# MainSchematic.net
KiCad netlist of a schematic drawn in Altium Designer
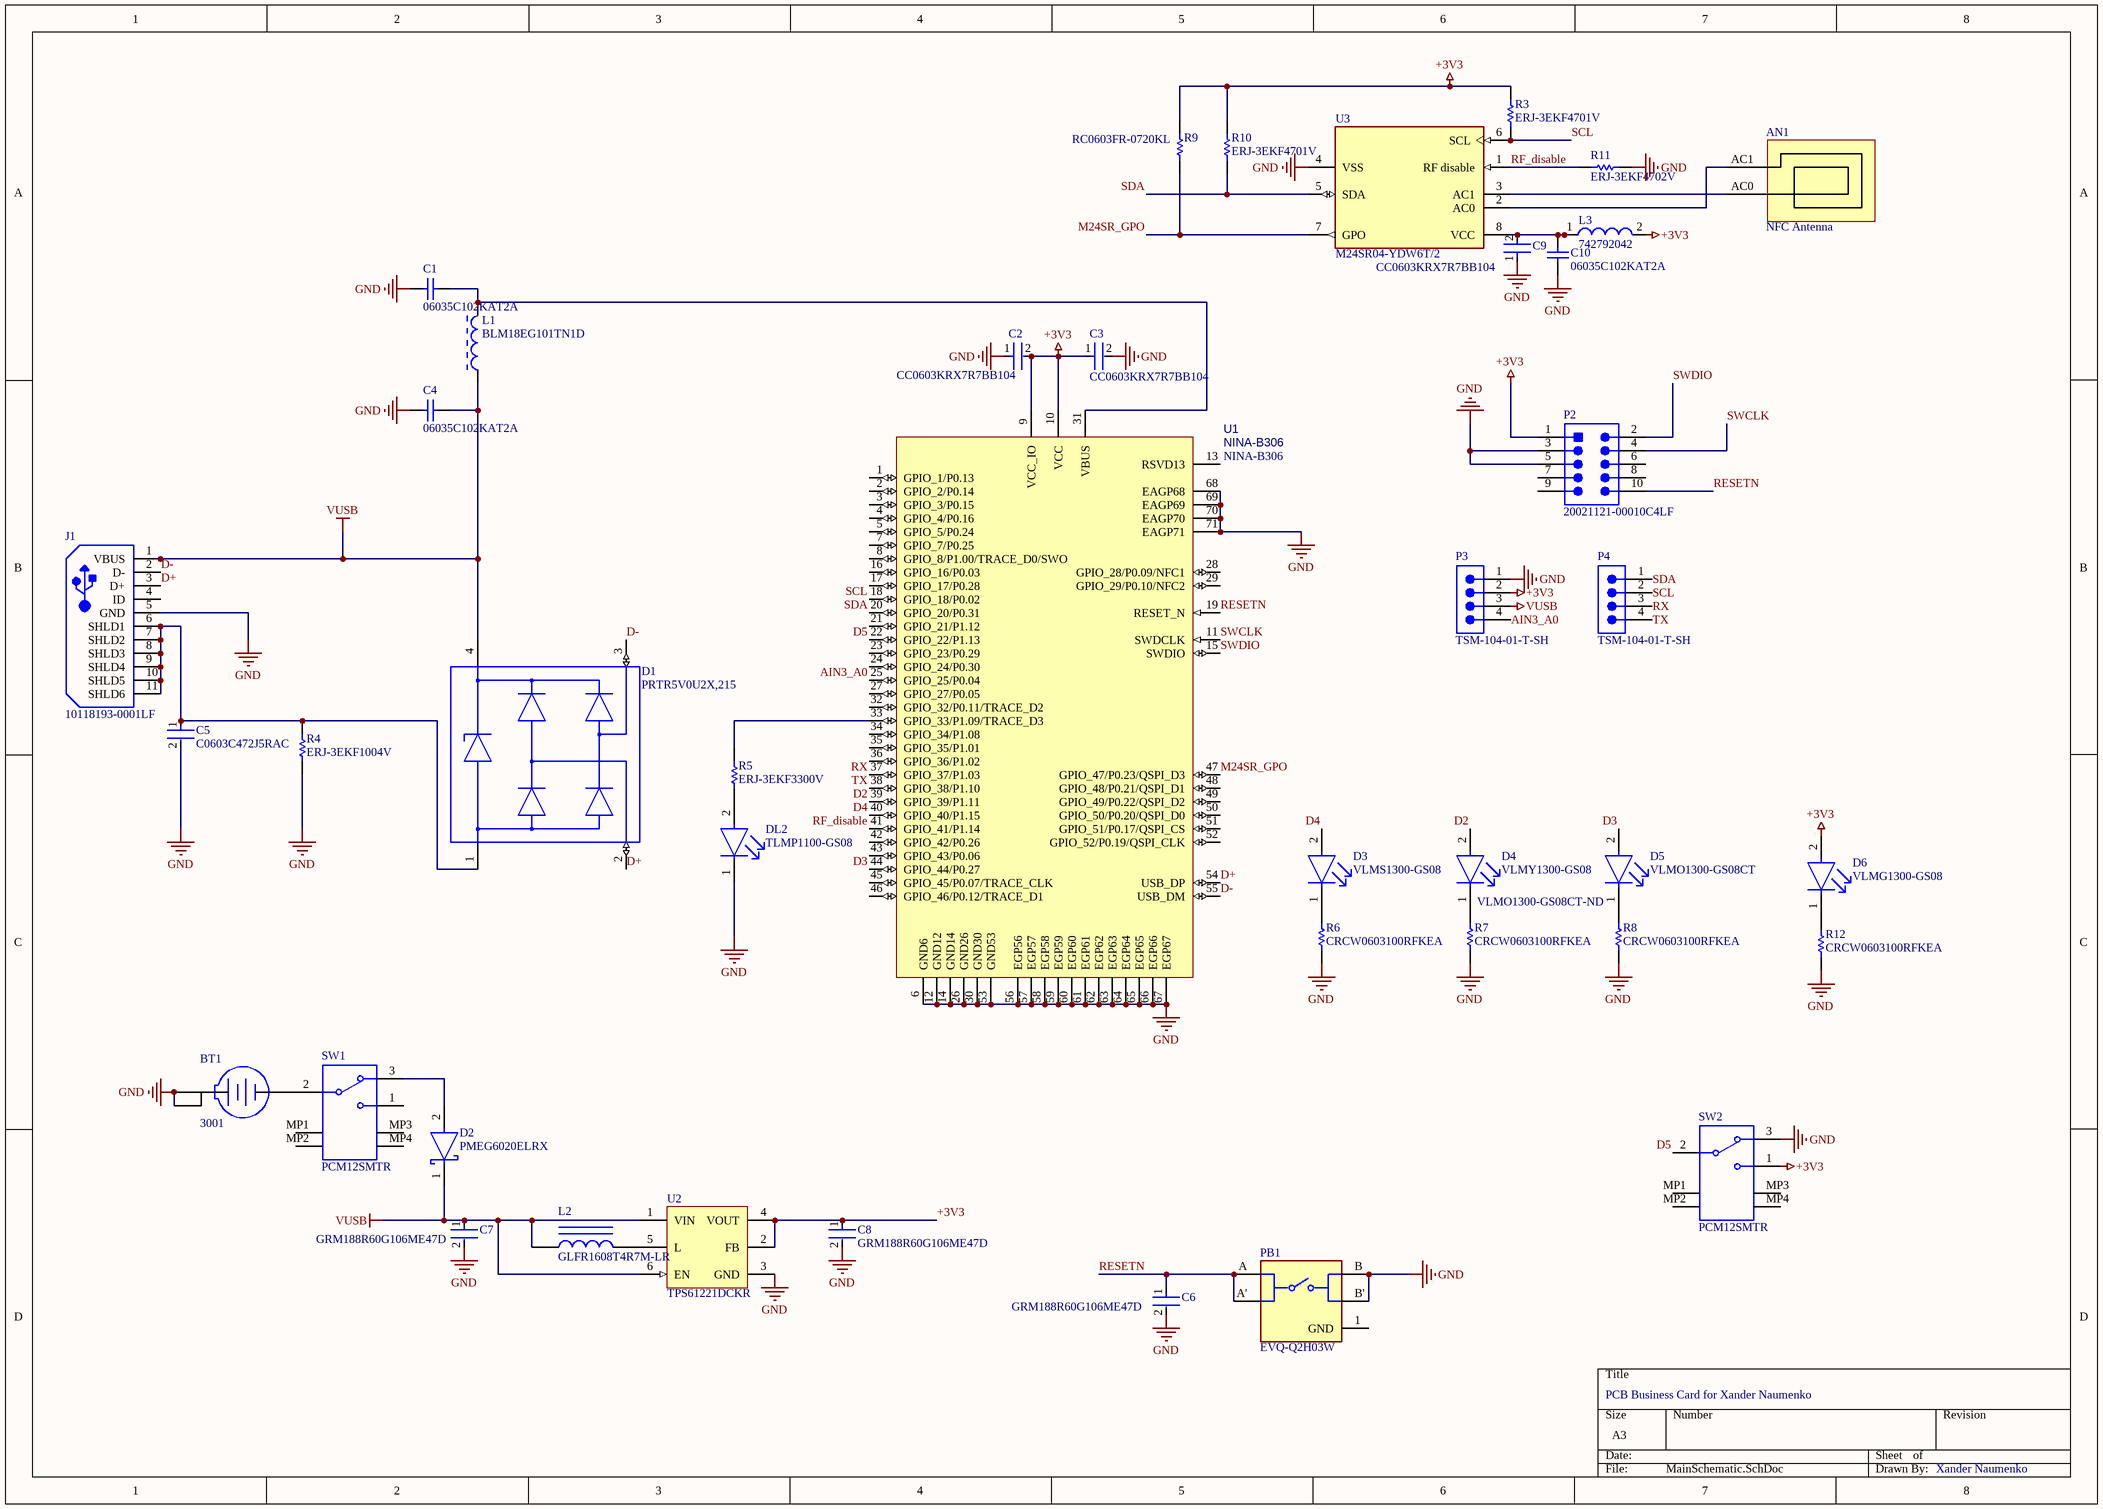
[diagram p0: MainSchematic.SchDoc]

(export (version "E")
  (design (tool "Eeschema 10.0.6"))
  (components
    (comp (ref "AN1")
      (value "NFC Antenna")
      (footprint "NFC_Antenna")
      (description "L=5.51 uH, tuned for 13.56 MHz")
      (libsource (lib "NFC_Antenna") (part "NFC_Antenna"))
    )
    (comp (ref "BT1")
      (value "3001")
      (footprint "KSTN-3001_V")
      (description "Holder Battery Coin, 12 mm, 2-Pin THD, RoHS")
      (fields (field (name "MANUFACTURER") "Keystone"))
      (libsource (lib "Altium Content Vault") (part "BATTERY-HOLDER-COIN-3"))
    )
    (comp (ref "C1")
      (value "06035C102KAT2A")
      (footprint "CAPC1608X90X35LL15T15")
      (fields (field (name "MANUFACTURER") "AVX Interconnect / Elco"))
      (libsource (lib "Altium Content Vault") (part "CAP"))
    )
    (comp (ref "C2")
      (value "CC0603KRX7R7BB104")
      (footprint "FP-CC0603-DA-MFG")
      (description "CAP CER 0.1UF 16V X7R 0603")
      (fields
        (field (name "OCTOPART") "https://octopart.com/cc0603krx7r7bb104-yageo-192941")
        (field (name "TOLERANCE") "0.1")
      )
      (libsource (lib "Altium Content Vault") (part "11868f565c42a9108669ba33697ecf6"))
    )
    (comp (ref "C3")
      (value "CC0603KRX7R7BB104")
      (footprint "FP-CC0603-DA-MFG")
      (description "CAP CER 0.1UF 16V X7R 0603")
      (fields
        (field (name "OCTOPART") "https://octopart.com/cc0603krx7r7bb104-yageo-192941")
        (field (name "TOLERANCE") "0.1")
      )
      (libsource (lib "Altium Content Vault") (part "11868f565c42a9108669ba33697ecf6"))
    )
    (comp (ref "C4")
      (value "06035C102KAT2A")
      (footprint "CAPC1608X90X35LL15T15")
      (fields (field (name "MANUFACTURER") "AVX Interconnect / Elco"))
      (libsource (lib "Altium Content Vault") (part "CAP"))
    )
    (comp (ref "C5")
      (value "C0603C472J5RAC")
      (footprint "FP-C0603C-CF-MFG")
      (description "C0603 4,700 pF X7R 30ppm/°C 5.00% 50 V")
      (fields
        (field (name "OCTOPART") "https://octopart.com/c0603c472j5rac-kemet-965121")
        (field (name "MANUFACTURER") "KEMET")
      )
      (libsource (lib "Altium Content Vault") (part "b4654b650e69147ec39a6b967a45e02"))
    )
    (comp (ref "C6")
      (value "GRM188R60G106ME47D")
      (footprint "FP-GRM188-0_1-e0_2_0_55-IPC_B")
      (description "Chip Multilayer Ceramic Capacitors for General Purpose, 0603, 10uF, X5R, 15%, 20%, 4V")
      (fields (field (name "TOLERANCE") "20%") (field (name "VOLTAGE") "4V"))
      (libsource (lib "Altium Content Vault") (part "02cd4be3c70576c341d710602a673aa"))
    )
    (comp (ref "C7")
      (value "GRM188R60G106ME47D")
      (footprint "FP-GRM188-0_1-e0_2_0_55-IPC_B")
      (description "Chip Multilayer Ceramic Capacitors for General Purpose, 0603, 10uF, X5R, 15%, 20%, 4V")
      (fields (field (name "TOLERANCE") "20%") (field (name "VOLTAGE") "4V"))
      (libsource (lib "Altium Content Vault") (part "02cd4be3c70576c341d710602a673aa"))
    )
    (comp (ref "C8")
      (value "GRM188R60G106ME47D")
      (footprint "FP-GRM188-0_1-e0_2_0_55-IPC_B")
      (description "Chip Multilayer Ceramic Capacitors for General Purpose, 0603, 10uF, X5R, 15%, 20%, 4V")
      (fields (field (name "TOLERANCE") "20%") (field (name "VOLTAGE") "4V"))
      (libsource (lib "Altium Content Vault") (part "02cd4be3c70576c341d710602a673aa"))
    )
    (comp (ref "C9")
      (value "CC0603KRX7R7BB104")
      (footprint "FP-CC0603-DA-MFG")
      (description "CAP CER 0.1UF 16V X7R 0603")
      (fields
        (field (name "OCTOPART") "https://octopart.com/cc0603krx7r7bb104-yageo-192941")
        (field (name "TOLERANCE") "0.1")
      )
      (libsource (lib "Altium Content Vault") (part "11868f565c42a9108669ba33697ecf6"))
    )
    (comp (ref "C10")
      (value "06035C102KAT2A")
      (footprint "CAPC1608X90X35LL15T15")
      (fields (field (name "MANUFACTURER") "AVX Interconnect / Elco"))
      (libsource (lib "Altium Content Vault") (part "CAP"))
    )
    (comp (ref "D1")
      (value "PRTR5V0U2X,215")
      (footprint "FP-SOT143B-MFG")
      (description "TVS DIODE 5.5V SOT143B")
      (fields (field (name "MANUFACTURER") "Nexperia"))
      (libsource (lib "Altium Content Vault") (part "31e4fa1655694efd507c8a671e666ef"))
    )
    (comp (ref "D2")
      (value "PMEG6020ELRX")
      (footprint "FP-SOD123W-MFG")
      (description "DIODE SCHOTTKY 60V 2A SOD123W")
      (libsource (lib "Altium Content Vault") (part "1d6ec82d83fb6aee721767c19dac4b9"))
    )
    (comp (ref "D3")
      (value "VLMS1300-GS08")
      (footprint "FP-6_541-5092_01-4-MFG")
      (description "Red 631nm LED Indication - Discrete 2V 0603 (1608 Metric)")
      (fields (field (name "MANUFACTURER") "Vishay"))
      (libsource (lib "Altium Content Vault") (part "8706943c75ba83719d021d2fdc84c58"))
    )
    (comp (ref "D4")
      (value "VLMY1300-GS08")
      (footprint "FP-6_541-5092_01-4-MFG")
      (description "LED YELLOW 0603 SMD")
      (fields
        (field (name "OCTOPART") "https://octopart.com/vlmy1300-gs08-vishay-21709204")
        (field (name "MANUFACTURER") "Vishay")
        (field (name "SUPPLIER PART NUMBER 1") "VLMO1300-GS08CT-ND")
      )
      (libsource (lib "Altium Content Vault") (part "8706943c75ba83719d021d2fdc84c58"))
    )
    (comp (ref "D5")
      (value "VLMO1300-GS08CT")
      (footprint "FP-6_541-5092_01-4-MFG")
      (description "LED YELLOW 0603 SMD")
      (fields
        (field (name "OCTOPART") "https://octopart.com/vlmy1300-gs08-vishay-21709204")
        (field (name "MANUFACTURER") "Vishay")
      )
      (libsource (lib "Altium Content Vault") (part "8706943c75ba83719d021d2fdc84c58"))
    )
    (comp (ref "D6")
      (value "VLMG1300-GS08")
      (footprint "FP-6_541-5092_01-4-MFG")
      (description "Green 571nm LED Indication - Discrete 2V 0603 (1608 Metric)")
      (fields (field (name "OCTOPART") "https://octopart.com/vlmg1300-gs08-vishay-21709199"))
      (libsource (lib "Altium Content Vault") (part "8706943c75ba83719d021d2fdc84c58"))
    )
    (comp (ref "DL2")
      (value "TLMP1100-GS08")
      (footprint "FP-6_541-5056_01-4-MFG")
      (description "LED GREEN 0603 SMD")
      (fields
        (field (name "MANUFACTURER") "Vishay")
        (field (name "OCTOPART") "https://octopart.com/tlmp1100-gs08-vishay-55433993")
      )
      (libsource (lib "Altium Content Vault") (part "8706943c75ba83719d021d2fdc84c58"))
    )
    (comp (ref "J1")
      (value "10118193-0001LF")
      (footprint "FCI-10118193-0001LF-5_V")
      (description "Micro USB B Type Receptacle, -55 to 85 degC, 5-Pin SMD, RoHS, Tape and Reel")
      (fields (field (name "MANUFACTURER") "FCI"))
      (libsource (lib "Altium Content Vault") (part "USB-5-6SHLD"))
    )
    (comp (ref "L1")
      (value "BLM18EG101TN1D")
      (footprint "MURA-BLM18-RF-H3-CHIP-2_V")
      (fields (field (name "MANUFACTURER") "Murata"))
      (libsource (lib "Altium Content Vault") (part "MURA-FB-2"))
    )
    (comp (ref "L2")
      (value "GLFR1608T4R7M-LR")
      (footprint "INDC1608X100X35LL20T15")
      (description "Chip Inductor, 4.7 uH, +/- 20%, -40 to 105 degC, 0603 (1608 Metric), RoHS, Tape and Reel")
      (fields (field (name "MANUFACTURER") "TDK") (field (name "TOLERANCE") "±20%"))
      (libsource (lib "Altium Content Vault") (part "IND-DOT-2_A"))
    )
    (comp (ref "L3")
      (value "742792042")
      (footprint "SMD-0805")
      (description "SMD EMI Suppression Ferrite Bead WE-CBF, Z = 600 Ohm")
      (libsource (lib "Altium Content Vault") (part "PAS-IND-INDUCTOR-2"))
    )
    (comp (ref "P2")
      (value "20021121-00010C4LF")
      (footprint "HDR2X5_SMT")
      (description "Male Header, Pitch 1.27 mm, 2 x 5 Position, Height 4.55 mm, -40 to 85 degC, RoHS, Tape and Reel")
      (fields (field (name "MANUFACTURER") "FCI"))
      (libsource (lib "Altium Content Vault") (part "CN-2P-M-R10"))
    )
    (comp (ref "P3")
      (value "TSM-104-01-T-SH")
      (footprint "SMTC-TSM-104-01-X-SH")
      (fields (field (name "MANUFACTURER") "Samtec"))
      (libsource (lib "Altium Content Vault") (part "SMTC-TSM-104-01-X-SH"))
    )
    (comp (ref "P4")
      (value "TSM-104-01-T-SH")
      (footprint "SMTC-TSM-104-01-X-SH")
      (fields (field (name "MANUFACTURER") "Samtec"))
      (libsource (lib "Altium Content Vault") (part "SMTC-TSM-104-01-X-SH"))
    )
    (comp (ref "PB1")
      (value "EVQ-Q2H03W")
      (footprint "FP-EVQ-Q2H03W-MFG")
      (description "SWITCH TACTILE SPST-NO 0.02A 15V")
      (fields
        (field (name "OCTOPART") "https://octopart.com/evq-q2h03w-panasonic-1368538")
        (field (name "MANUFACTURER") "Panasonic Electronic Components")
      )
      (libsource (lib "Altium Content Vault") (part "771f9546cad75bebae6a9b98152ef8d"))
    )
    (comp (ref "R3")
      (value "ERJ-3EKF4701V")
      (footprint "RESC1608X55X30NL15T15")
      (fields (field (name "TOLERANCE") "5%"))
      (libsource (lib "Altium Content Vault") (part "RES-2"))
    )
    (comp (ref "R4")
      (value "ERJ-3EKF1004V")
      (footprint "RESC1608X55X30LL15T15")
      (fields (field (name "MANUFACTURER") "Panasonic"))
      (libsource (lib "Altium Content Vault") (part "RES"))
    )
    (comp (ref "R5")
      (value "ERJ-3EKF3300V")
      (footprint "RESC1608X55X30LL15T15")
      (description "Chip Resistor, 330 Ohm, +/- 1%, 0.1 W, -55 to 155 degC, 0603 (1608 Metric), RoHS, Tape and Reel")
      (libsource (lib "Altium Content Vault") (part "RES-2"))
    )
    (comp (ref "R6")
      (value "CRCW0603100RFKEA")
      (footprint "RESC1609X50X30ML8T20")
      (description "Chip Resistor, 100 Ohm, +/- 1%, 100 mW,-55 to 155 degC, 0603 (1608 Metric), RoHS, Tape and Ree")
      (fields (field (name "MANUFACTURER") "Vishay Semiconductor"))
      (libsource (lib "Altium Content Vault") (part "RES-2"))
    )
    (comp (ref "R7")
      (value "CRCW0603100RFKEA")
      (footprint "RESC1609X50X30ML8T20")
      (description "Chip Resistor, 100 Ohm, +/- 1%, 100 mW,-55 to 155 degC, 0603 (1608 Metric), RoHS, Tape and Ree")
      (fields (field (name "MANUFACTURER") "Vishay Semiconductor"))
      (libsource (lib "Altium Content Vault") (part "RES-2"))
    )
    (comp (ref "R8")
      (value "CRCW0603100RFKEA")
      (footprint "RESC1609X50X30ML8T20")
      (description "Chip Resistor, 100 Ohm, +/- 1%, 100 mW,-55 to 155 degC, 0603 (1608 Metric), RoHS, Tape and Ree")
      (fields (field (name "MANUFACTURER") "Vishay Semiconductor"))
      (libsource (lib "Altium Content Vault") (part "RES-2"))
    )
    (comp (ref "R9")
      (value "RC0603FR-0720KL")
      (footprint "RESC1608X55X25LL10T15")
      (description "Chip Resistor, 20 KOhm, +/- 1%, 0.1 W, -55 to 155 degC, 0603 (1608 Metric), RoHS, Tape and Reel")
      (fields (field (name "MANUFACTURER") "Yageo") (field (name "TOLERANCE") "1%"))
      (libsource (lib "Altium Content Vault") (part "RES-2"))
    )
    (comp (ref "R10")
      (value "ERJ-3EKF4701V")
      (footprint "RESC1608X55X30NL15T15")
      (fields (field (name "TOLERANCE") "5%"))
      (libsource (lib "Altium Content Vault") (part "RES-2"))
    )
    (comp (ref "R11")
      (value "ERJ-3EKF4702V")
      (footprint "RESC1608X55X30NL15T15")
      (description "Chip Resistor, 47 KOhm, +/- 1%, 0.1 W, -55 to 155 degC, 0603 (1608 Metric), RoHS, Tape and Reel")
      (libsource (lib "Altium Content Vault") (part "RES-2"))
    )
    (comp (ref "R12")
      (value "CRCW0603100RFKEA")
      (footprint "RESC1609X50X30ML8T20")
      (description "Chip Resistor, 100 Ohm, +/- 1%, 100 mW,-55 to 155 degC, 0603 (1608 Metric), RoHS, Tape and Ree")
      (fields (field (name "MANUFACTURER") "Vishay Semiconductor"))
      (libsource (lib "Altium Content Vault") (part "RES-2"))
    )
    (comp (ref "SW1")
      (value "PCM12SMTR")
      (footprint "CKCP-PCM12SMTR_V")
      (description "Ultraminiature Slide Switch, SPDT, 0.3 A, 6 V, -20 to 85 degC, 3-Pin SMD, RoHS, Tape and Reel")
      (fields (field (name "MANUFACTURER") "C&K Components"))
      (libsource (lib "Altium Content Vault") (part "SW-SPDT-3_A"))
    )
    (comp (ref "SW2")
      (value "PCM12SMTR")
      (footprint "CKCP-PCM12SMTR_V")
      (description "Ultraminiature Slide Switch, SPDT, 0.3 A, 6 V, -20 to 85 degC, 3-Pin SMD, RoHS, Tape and Reel")
      (fields (field (name "MANUFACTURER") "C&K Components"))
      (libsource (lib "Altium Content Vault") (part "SW-SPDT-3_A"))
    )
    (comp (ref "U1")
      (value "NINA-B306")
      (footprint "NINA_LGA71R_1500X1000X223_PCB")
      (description "Stand-alone Bluetooth low energy module")
      (fields (field (name "MANUFACTURER") "u-blox") (field (name "ALTIUM_VALUE") "NINA-B306"))
      (libsource (lib "ubloxLib") (part "NINA-B306"))
    )
    (comp (ref "U2")
      (value "TPS61221DCKR")
      (footprint "DCK0006A_L")
      (fields (field (name "MANUFACTURER") "Texas Instruments"))
      (libsource (lib "Altium Content Vault") (part "TI-TPS61221DCK6"))
    )
    (comp (ref "U3")
      (value "M24SR04-YDW6T/2")
      (footprint "FP-TSSOP8-AM-IPC_C")
      (description "IC RFID TRANSP 13.56MHZ 8TSSOP")
      (fields
        (field (name "OCTOPART") "https://octopart.com/m24sr04-ydw6t%2F2-stmicroelectronics-31443742")
        (field (name "MANUFACTURER") "STMicroelectronics")
      )
      (libsource (lib "Altium Content Vault") (part "34dd642e2aae41d6824d9e49441a900"))
    )
  )
  (nets
    (net (code "1") (name "+3V3") (class "Default")
      (node (ref "C2") (pin "2") (pinfunction "2_2") (pintype "passive"))
      (node (ref "C3") (pin "1") (pinfunction "1_1") (pintype "passive"))
      (node (ref "C8") (pin "1") (pinfunction "1_1") (pintype "passive"))
      (node (ref "D6") (pin "2") (pinfunction "A_2") (pintype "passive"))
      (node (ref "L3") (pin "2") (pinfunction "2_2") (pintype "passive"))
      (node (ref "P2") (pin "1") (pinfunction "1_1") (pintype "passive"))
      (node (ref "P3") (pin "2") (pinfunction "2_2") (pintype "passive"))
      (node (ref "R10") (pin "2") (pinfunction "2_2") (pintype "passive"))
      (node (ref "R3") (pin "2") (pinfunction "2_2") (pintype "passive"))
      (node (ref "R9") (pin "2") (pinfunction "2_2") (pintype "passive"))
      (node (ref "SW2") (pin "1") (pinfunction "1_1") (pintype "passive"))
      (node (ref "U1") (pin "10") (pinfunction "VCC_10") (pintype "power_in"))
      (node (ref "U1") (pin "9") (pinfunction "VCC_IO_9") (pintype "power_in"))
      (node (ref "U2") (pin "2") (pinfunction "FB_2") (pintype "passive"))
      (node (ref "U2") (pin "4") (pinfunction "VOUT_4") (pintype "power_in"))
    )
    (net (code "2") (name "/AIN3_A0") (class "Default")
      (node (ref "P3") (pin "4") (pinfunction "4_4") (pintype "passive"))
      (node (ref "U1") (pin "25") (pinfunction "GPIO_25/P0.04_25") (pintype "bidirectional"))
    )
    (net (code "3") (name "/D+") (class "Default")
      (node (ref "D1") (pin "2") (pinfunction "I/O_1_2") (pintype "bidirectional"))
      (node (ref "J1") (pin "3") (pinfunction "D+_3") (pintype "passive"))
      (node (ref "U1") (pin "54") (pinfunction "USB_DP_54") (pintype "bidirectional"))
    )
    (net (code "4") (name "/D-") (class "Default")
      (node (ref "D1") (pin "3") (pinfunction "I/O_2_3") (pintype "bidirectional"))
      (node (ref "J1") (pin "2") (pinfunction "D-_2") (pintype "passive"))
      (node (ref "U1") (pin "55") (pinfunction "USB_DM_55") (pintype "bidirectional"))
    )
    (net (code "5") (name "/D2") (class "Default")
      (node (ref "D4") (pin "2") (pinfunction "A_2") (pintype "passive"))
      (node (ref "U1") (pin "39") (pinfunction "GPIO_39/P1.11_39") (pintype "bidirectional"))
    )
    (net (code "6") (name "/D3") (class "Default")
      (node (ref "D5") (pin "2") (pinfunction "A_2") (pintype "passive"))
      (node (ref "U1") (pin "44") (pinfunction "GPIO_44/P0.27_44") (pintype "bidirectional"))
    )
    (net (code "7") (name "/D4") (class "Default")
      (node (ref "D3") (pin "2") (pinfunction "A_2") (pintype "passive"))
      (node (ref "U1") (pin "40") (pinfunction "GPIO_40/P1.15_40") (pintype "bidirectional"))
    )
    (net (code "8") (name "/D5") (class "Default")
      (node (ref "SW2") (pin "2") (pinfunction "2_2") (pintype "passive"))
      (node (ref "U1") (pin "22") (pinfunction "GPIO_22/P1.13_22") (pintype "bidirectional"))
    )
    (net (code "9") (name "/M24SR_GPO") (class "Default")
      (node (ref "R9") (pin "1") (pinfunction "1_1") (pintype "passive"))
      (node (ref "U1") (pin "47") (pinfunction "GPIO_47/P0.23/QSPI_D3_47") (pintype "bidirectional"))
      (node (ref "U3") (pin "7") (pinfunction "GPO_7") (pintype "output"))
    )
    (net (code "10") (name "/RESETN") (class "Default")
      (node (ref "C6") (pin "1") (pinfunction "1_1") (pintype "passive"))
      (node (ref "P2") (pin "10") (pinfunction "10_10") (pintype "passive"))
      (node (ref "PB1") (pin "A") (pinfunction "A_A") (pintype "passive"))
      (node (ref "PB1") (pin "A'") (pinfunction "A'_A'") (pintype "passive"))
      (node (ref "U1") (pin "19") (pinfunction "RESET_N_19") (pintype "input"))
    )
    (net (code "11") (name "/RF_disable") (class "Default")
      (node (ref "R11") (pin "1") (pinfunction "1_1") (pintype "passive"))
      (node (ref "U1") (pin "41") (pinfunction "GPIO_41/P1.14_41") (pintype "bidirectional"))
      (node (ref "U3") (pin "1") (pinfunction "RF_disable_1") (pintype "input"))
    )
    (net (code "12") (name "/RX") (class "Default")
      (node (ref "P4") (pin "3") (pinfunction "3_3") (pintype "passive"))
      (node (ref "U1") (pin "37") (pinfunction "GPIO_37/P1.03_37") (pintype "bidirectional"))
    )
    (net (code "13") (name "/SCL") (class "Default")
      (node (ref "P4") (pin "2") (pinfunction "2_2") (pintype "passive"))
      (node (ref "R3") (pin "1") (pinfunction "1_1") (pintype "passive"))
      (node (ref "U1") (pin "18") (pinfunction "GPIO_18/P0.02_18") (pintype "bidirectional"))
      (node (ref "U3") (pin "6") (pinfunction "SCL_6") (pintype "input"))
    )
    (net (code "14") (name "/SDA") (class "Default")
      (node (ref "P4") (pin "1") (pinfunction "1_1") (pintype "passive"))
      (node (ref "R10") (pin "1") (pinfunction "1_1") (pintype "passive"))
      (node (ref "U1") (pin "20") (pinfunction "GPIO_20/P0.31_20") (pintype "bidirectional"))
      (node (ref "U3") (pin "5") (pinfunction "SDA_5") (pintype "bidirectional"))
    )
    (net (code "15") (name "/SWCLK") (class "Default")
      (node (ref "P2") (pin "4") (pinfunction "4_4") (pintype "passive"))
      (node (ref "U1") (pin "11") (pinfunction "SWDCLK_11") (pintype "input"))
    )
    (net (code "16") (name "/SWDIO") (class "Default")
      (node (ref "P2") (pin "2") (pinfunction "2_2") (pintype "passive"))
      (node (ref "U1") (pin "15") (pinfunction "SWDIO_15") (pintype "bidirectional"))
    )
    (net (code "17") (name "/TX") (class "Default")
      (node (ref "P4") (pin "4") (pinfunction "4_4") (pintype "passive"))
      (node (ref "U1") (pin "38") (pinfunction "GPIO_38/P1.10_38") (pintype "bidirectional"))
    )
    (net (code "18") (name "GND") (class "Default")
      (node (ref "BT1") (pin "1") (pinfunction "+_1") (pintype "passive"))
      (node (ref "BT1") (pin "2") (pinfunction "+_2") (pintype "passive"))
      (node (ref "C1") (pin "1") (pinfunction "1_1") (pintype "passive"))
      (node (ref "C10") (pin "1") (pinfunction "1_1") (pintype "passive"))
      (node (ref "C2") (pin "1") (pinfunction "1_1") (pintype "passive"))
      (node (ref "C3") (pin "2") (pinfunction "2_2") (pintype "passive"))
      (node (ref "C4") (pin "1") (pinfunction "1_1") (pintype "passive"))
      (node (ref "C5") (pin "2") (pinfunction "2_2") (pintype "passive"))
      (node (ref "C6") (pin "2") (pinfunction "2_2") (pintype "passive"))
      (node (ref "C7") (pin "2") (pinfunction "2_2") (pintype "passive"))
      (node (ref "C8") (pin "2") (pinfunction "2_2") (pintype "passive"))
      (node (ref "C9") (pin "1") (pinfunction "1_1") (pintype "passive"))
      (node (ref "DL2") (pin "1") (pinfunction "C_1") (pintype "passive"))
      (node (ref "J1") (pin "5") (pinfunction "GND_5") (pintype "passive"))
      (node (ref "P2") (pin "3") (pinfunction "3_3") (pintype "passive"))
      (node (ref "P2") (pin "5") (pinfunction "5_5") (pintype "passive"))
      (node (ref "P3") (pin "1") (pinfunction "1_1") (pintype "passive"))
      (node (ref "PB1") (pin "B") (pinfunction "B_B") (pintype "passive"))
      (node (ref "PB1") (pin "B'") (pinfunction "B'_B'") (pintype "passive"))
      (node (ref "R11") (pin "2") (pinfunction "2_2") (pintype "passive"))
      (node (ref "R12") (pin "1") (pinfunction "1_1") (pintype "passive"))
      (node (ref "R4") (pin "1") (pinfunction "1_1") (pintype "passive"))
      (node (ref "R6") (pin "1") (pinfunction "1_1") (pintype "passive"))
      (node (ref "R7") (pin "1") (pinfunction "1_1") (pintype "passive"))
      (node (ref "R8") (pin "1") (pinfunction "1_1") (pintype "passive"))
      (node (ref "SW2") (pin "3") (pinfunction "3_3") (pintype "passive"))
      (node (ref "U1") (pin "12") (pinfunction "GND12_12") (pintype "power_in"))
      (node (ref "U1") (pin "14") (pinfunction "GND14_14") (pintype "power_in"))
      (node (ref "U1") (pin "26") (pinfunction "GND26_26") (pintype "power_in"))
      (node (ref "U1") (pin "30") (pinfunction "GND30_30") (pintype "power_in"))
      (node (ref "U1") (pin "53") (pinfunction "GND53_53") (pintype "power_in"))
      (node (ref "U1") (pin "56") (pinfunction "EGP56_56") (pintype "power_in"))
      (node (ref "U1") (pin "57") (pinfunction "EGP57_57") (pintype "power_in"))
      (node (ref "U1") (pin "58") (pinfunction "EGP58_58") (pintype "power_in"))
      (node (ref "U1") (pin "59") (pinfunction "EGP59_59") (pintype "power_in"))
      (node (ref "U1") (pin "6") (pinfunction "GND6_6") (pintype "power_in"))
      (node (ref "U1") (pin "60") (pinfunction "EGP60_60") (pintype "power_in"))
      (node (ref "U1") (pin "61") (pinfunction "EGP61_61") (pintype "power_in"))
      (node (ref "U1") (pin "62") (pinfunction "EGP62_62") (pintype "power_in"))
      (node (ref "U1") (pin "63") (pinfunction "EGP63_63") (pintype "power_in"))
      (node (ref "U1") (pin "64") (pinfunction "EGP64_64") (pintype "power_in"))
      (node (ref "U1") (pin "65") (pinfunction "EGP65_65") (pintype "power_in"))
      (node (ref "U1") (pin "66") (pinfunction "EGP66_66") (pintype "power_in"))
      (node (ref "U1") (pin "67") (pinfunction "EGP67_67") (pintype "power_in"))
      (node (ref "U1") (pin "68") (pinfunction "EAGP68_68") (pintype "power_in"))
      (node (ref "U1") (pin "69") (pinfunction "EAGP69_69") (pintype "power_in"))
      (node (ref "U1") (pin "70") (pinfunction "EAGP70_70") (pintype "power_in"))
      (node (ref "U1") (pin "71") (pinfunction "EAGP71_71") (pintype "power_in"))
      (node (ref "U2") (pin "3") (pinfunction "GND_3") (pintype "power_in"))
      (node (ref "U3") (pin "4") (pinfunction "VSS_4") (pintype "power_in"))
    )
    (net (code "19") (name "Net-(BT1--)") (class "Default")
      (node (ref "BT1") (pin "3") (pinfunction "-_3") (pintype "passive"))
      (node (ref "SW1") (pin "2") (pinfunction "2_2") (pintype "passive"))
    )
    (net (code "20") (name "Net-(D1-GND)") (class "Default")
      (node (ref "C5") (pin "1") (pinfunction "1_1") (pintype "passive"))
      (node (ref "D1") (pin "1") (pinfunction "GND_1") (pintype "power_in"))
      (node (ref "J1") (pin "10") (pinfunction "SHLD5_10") (pintype "passive"))
      (node (ref "J1") (pin "11") (pinfunction "SHLD6_11") (pintype "passive"))
      (node (ref "J1") (pin "6") (pinfunction "SHLD1_6") (pintype "passive"))
      (node (ref "J1") (pin "7") (pinfunction "SHLD2_7") (pintype "passive"))
      (node (ref "J1") (pin "8") (pinfunction "SHLD3_8") (pintype "passive"))
      (node (ref "J1") (pin "9") (pinfunction "SHLD4_9") (pintype "passive"))
      (node (ref "R4") (pin "2") (pinfunction "2_2") (pintype "passive"))
    )
    (net (code "21") (name "Net-(D2-A)") (class "Default")
      (node (ref "D2") (pin "2") (pinfunction "A_2") (pintype "passive"))
      (node (ref "SW1") (pin "3") (pinfunction "3_3") (pintype "passive"))
    )
    (net (code "22") (name "Net-(D3-C)") (class "Default")
      (node (ref "D3") (pin "1") (pinfunction "C_1") (pintype "passive"))
      (node (ref "R6") (pin "2") (pinfunction "2_2") (pintype "passive"))
    )
    (net (code "23") (name "Net-(D4-C)") (class "Default")
      (node (ref "D4") (pin "1") (pinfunction "C_1") (pintype "passive"))
      (node (ref "R7") (pin "2") (pinfunction "2_2") (pintype "passive"))
    )
    (net (code "24") (name "Net-(D5-C)") (class "Default")
      (node (ref "D5") (pin "1") (pinfunction "C_1") (pintype "passive"))
      (node (ref "R8") (pin "2") (pinfunction "2_2") (pintype "passive"))
    )
    (net (code "25") (name "Net-(D6-C)") (class "Default")
      (node (ref "D6") (pin "1") (pinfunction "C_1") (pintype "passive"))
      (node (ref "R12") (pin "2") (pinfunction "2_2") (pintype "passive"))
    )
    (net (code "26") (name "Net-(DL2-A)") (class "Default")
      (node (ref "DL2") (pin "2") (pinfunction "A_2") (pintype "passive"))
      (node (ref "R5") (pin "1") (pinfunction "1_1") (pintype "passive"))
    )
    (net (code "27") (name "Net-(U1-GPIO_33{slash}P1.09{slash}TRACE_D3)") (class "Default")
      (node (ref "R5") (pin "2") (pinfunction "2_2") (pintype "passive"))
      (node (ref "U1") (pin "33") (pinfunction "GPIO_33/P1.09/TRACE_D3_33") (pintype "bidirectional"))
    )
    (net (code "28") (name "Net-(U1-VBUS)") (class "Default")
      (node (ref "C1") (pin "2") (pinfunction "2_2") (pintype "passive"))
      (node (ref "L1") (pin "2") (pinfunction "2_2") (pintype "passive"))
      (node (ref "U1") (pin "31") (pinfunction "VBUS_31") (pintype "power_in"))
    )
    (net (code "29") (name "Net-(U2-L)") (class "Default")
      (node (ref "L2") (pin "2") (pinfunction "2_2") (pintype "passive"))
      (node (ref "U2") (pin "5") (pinfunction "L_5") (pintype "power_in"))
    )
    (net (code "30") (name "Net-(U3-AC0)") (class "Default")
      (node (ref "AN1") (pin "AC1") (pintype "passive"))
      (node (ref "U3") (pin "2") (pinfunction "AC0_2") (pintype "passive"))
    )
    (net (code "31") (name "Net-(U3-AC1)") (class "Default")
      (node (ref "AN1") (pin "AC0") (pintype "passive"))
      (node (ref "U3") (pin "3") (pinfunction "AC1_3") (pintype "passive"))
    )
    (net (code "32") (name "Net-(U3-VCC)") (class "Default")
      (node (ref "C10") (pin "2") (pinfunction "2_2") (pintype "passive"))
      (node (ref "C9") (pin "2") (pinfunction "2_2") (pintype "passive"))
      (node (ref "L3") (pin "1") (pinfunction "1_1") (pintype "passive"))
      (node (ref "U3") (pin "8") (pinfunction "VCC_8") (pintype "power_in"))
    )
    (net (code "33") (name "VUSB") (class "Default")
      (node (ref "C4") (pin "2") (pinfunction "2_2") (pintype "passive"))
      (node (ref "C7") (pin "1") (pinfunction "1_1") (pintype "passive"))
      (node (ref "D1") (pin "4") (pinfunction "VCC_4") (pintype "power_in"))
      (node (ref "D2") (pin "1") (pinfunction "C_1") (pintype "passive"))
      (node (ref "J1") (pin "1") (pinfunction "VBUS_1") (pintype "passive"))
      (node (ref "L1") (pin "1") (pinfunction "1_1") (pintype "passive"))
      (node (ref "L2") (pin "1") (pinfunction "1_1") (pintype "passive"))
      (node (ref "P3") (pin "3") (pinfunction "3_3") (pintype "passive"))
      (node (ref "U2") (pin "1") (pinfunction "VIN_1") (pintype "power_in"))
      (node (ref "U2") (pin "6") (pinfunction "EN_6") (pintype "input"))
    )
    (net (code "34") (name "unconnected-(J1-ID-Pad4)") (class "Default")
      (node (ref "J1") (pin "4") (pinfunction "ID_4") (pintype "passive"))
    )
    (net (code "35") (name "unconnected-(P2-Pad6)") (class "Default")
      (node (ref "P2") (pin "6") (pinfunction "6_6") (pintype "passive"))
    )
    (net (code "36") (name "unconnected-(P2-Pad7)") (class "Default")
      (node (ref "P2") (pin "7") (pinfunction "7_7") (pintype "passive"))
    )
    (net (code "37") (name "unconnected-(P2-Pad8)") (class "Default")
      (node (ref "P2") (pin "8") (pinfunction "8_8") (pintype "passive"))
    )
    (net (code "38") (name "unconnected-(P2-Pad9)") (class "Default")
      (node (ref "P2") (pin "9") (pinfunction "9_9") (pintype "passive"))
    )
    (net (code "39") (name "unconnected-(PB1-GND-Pad1)") (class "Default")
      (node (ref "PB1") (pin "1") (pinfunction "GND_1") (pintype "power_in"))
    )
    (net (code "40") (name "unconnected-(SW1-Pad1)") (class "Default")
      (node (ref "SW1") (pin "1") (pinfunction "1_1") (pintype "passive"))
    )
    (net (code "41") (name "unconnected-(SW1-PadMP1)") (class "Default")
      (node (ref "SW1") (pin "MP1") (pinfunction "MP1_MP1") (pintype "passive"))
    )
    (net (code "42") (name "unconnected-(SW1-PadMP2)") (class "Default")
      (node (ref "SW1") (pin "MP2") (pinfunction "MP2_MP2") (pintype "passive"))
    )
    (net (code "43") (name "unconnected-(SW1-PadMP3)") (class "Default")
      (node (ref "SW1") (pin "MP3") (pinfunction "MP3_MP3") (pintype "passive"))
    )
    (net (code "44") (name "unconnected-(SW1-PadMP4)") (class "Default")
      (node (ref "SW1") (pin "MP4") (pinfunction "MP4_MP4") (pintype "passive"))
    )
    (net (code "45") (name "unconnected-(SW2-PadMP1)") (class "Default")
      (node (ref "SW2") (pin "MP1") (pinfunction "MP1_MP1") (pintype "passive"))
    )
    (net (code "46") (name "unconnected-(SW2-PadMP2)") (class "Default")
      (node (ref "SW2") (pin "MP2") (pinfunction "MP2_MP2") (pintype "passive"))
    )
    (net (code "47") (name "unconnected-(SW2-PadMP3)") (class "Default")
      (node (ref "SW2") (pin "MP3") (pinfunction "MP3_MP3") (pintype "passive"))
    )
    (net (code "48") (name "unconnected-(SW2-PadMP4)") (class "Default")
      (node (ref "SW2") (pin "MP4") (pinfunction "MP4_MP4") (pintype "passive"))
    )
    (net (code "49") (name "unconnected-(U1-GPIO_1{slash}P0.13-Pad1)") (class "Default")
      (node (ref "U1") (pin "1") (pinfunction "GPIO_1/P0.13_1") (pintype "bidirectional"))
    )
    (net (code "50") (name "unconnected-(U1-GPIO_2{slash}P0.14-Pad2)") (class "Default")
      (node (ref "U1") (pin "2") (pinfunction "GPIO_2/P0.14_2") (pintype "bidirectional"))
    )
    (net (code "51") (name "unconnected-(U1-GPIO_3{slash}P0.15-Pad3)") (class "Default")
      (node (ref "U1") (pin "3") (pinfunction "GPIO_3/P0.15_3") (pintype "bidirectional"))
    )
    (net (code "52") (name "unconnected-(U1-GPIO_4{slash}P0.16-Pad4)") (class "Default")
      (node (ref "U1") (pin "4") (pinfunction "GPIO_4/P0.16_4") (pintype "bidirectional"))
    )
    (net (code "53") (name "unconnected-(U1-GPIO_5{slash}P0.24-Pad5)") (class "Default")
      (node (ref "U1") (pin "5") (pinfunction "GPIO_5/P0.24_5") (pintype "bidirectional"))
    )
    (net (code "54") (name "unconnected-(U1-GPIO_7{slash}P0.25-Pad7)") (class "Default")
      (node (ref "U1") (pin "7") (pinfunction "GPIO_7/P0.25_7") (pintype "bidirectional"))
    )
    (net (code "55") (name "unconnected-(U1-GPIO_8{slash}P1.00{slash}TRACE_D0{slash}SWO-Pad8)") (class "Default")
      (node (ref "U1") (pin "8") (pinfunction "GPIO_8/P1.00/TRACE_D0/SWO_8") (pintype "bidirectional"))
    )
    (net (code "56") (name "unconnected-(U1-GPIO_16{slash}P0.03-Pad16)") (class "Default")
      (node (ref "U1") (pin "16") (pinfunction "GPIO_16/P0.03_16") (pintype "bidirectional"))
    )
    (net (code "57") (name "unconnected-(U1-GPIO_17{slash}P0.28-Pad17)") (class "Default")
      (node (ref "U1") (pin "17") (pinfunction "GPIO_17/P0.28_17") (pintype "bidirectional"))
    )
    (net (code "58") (name "unconnected-(U1-GPIO_21{slash}P1.12-Pad21)") (class "Default")
      (node (ref "U1") (pin "21") (pinfunction "GPIO_21/P1.12_21") (pintype "bidirectional"))
    )
    (net (code "59") (name "unconnected-(U1-GPIO_23{slash}P0.29-Pad23)") (class "Default")
      (node (ref "U1") (pin "23") (pinfunction "GPIO_23/P0.29_23") (pintype "bidirectional"))
    )
    (net (code "60") (name "unconnected-(U1-GPIO_24{slash}P0.30-Pad24)") (class "Default")
      (node (ref "U1") (pin "24") (pinfunction "GPIO_24/P0.30_24") (pintype "bidirectional"))
    )
    (net (code "61") (name "unconnected-(U1-GPIO_27{slash}P0.05-Pad27)") (class "Default")
      (node (ref "U1") (pin "27") (pinfunction "GPIO_27/P0.05_27") (pintype "bidirectional"))
    )
    (net (code "62") (name "unconnected-(U1-GPIO_28{slash}P0.09{slash}NFC1-Pad28)") (class "Default")
      (node (ref "U1") (pin "28") (pinfunction "GPIO_28/P0.09/NFC1_28") (pintype "bidirectional"))
    )
    (net (code "63") (name "unconnected-(U1-GPIO_29{slash}P0.10{slash}NFC2-Pad29)") (class "Default")
      (node (ref "U1") (pin "29") (pinfunction "GPIO_29/P0.10/NFC2_29") (pintype "bidirectional"))
    )
    (net (code "64") (name "unconnected-(U1-GPIO_32{slash}P0.11{slash}TRACE_D2-Pad32)") (class "Default")
      (node (ref "U1") (pin "32") (pinfunction "GPIO_32/P0.11/TRACE_D2_32") (pintype "bidirectional"))
    )
    (net (code "65") (name "unconnected-(U1-GPIO_34{slash}P1.08-Pad34)") (class "Default")
      (node (ref "U1") (pin "34") (pinfunction "GPIO_34/P1.08_34") (pintype "bidirectional"))
    )
    (net (code "66") (name "unconnected-(U1-GPIO_35{slash}P1.01-Pad35)") (class "Default")
      (node (ref "U1") (pin "35") (pinfunction "GPIO_35/P1.01_35") (pintype "bidirectional"))
    )
    (net (code "67") (name "unconnected-(U1-GPIO_36{slash}P1.02-Pad36)") (class "Default")
      (node (ref "U1") (pin "36") (pinfunction "GPIO_36/P1.02_36") (pintype "bidirectional"))
    )
    (net (code "68") (name "unconnected-(U1-GPIO_42{slash}P0.26-Pad42)") (class "Default")
      (node (ref "U1") (pin "42") (pinfunction "GPIO_42/P0.26_42") (pintype "bidirectional"))
    )
    (net (code "69") (name "unconnected-(U1-GPIO_43{slash}P0.06-Pad43)") (class "Default")
      (node (ref "U1") (pin "43") (pinfunction "GPIO_43/P0.06_43") (pintype "bidirectional"))
    )
    (net (code "70") (name "unconnected-(U1-GPIO_45{slash}P0.07{slash}TRACE_CLK-Pad45)") (class "Default")
      (node (ref "U1") (pin "45") (pinfunction "GPIO_45/P0.07/TRACE_CLK_45") (pintype "bidirectional"))
    )
    (net (code "71") (name "unconnected-(U1-GPIO_46{slash}P0.12{slash}TRACE_D1-Pad46)") (class "Default")
      (node (ref "U1") (pin "46") (pinfunction "GPIO_46/P0.12/TRACE_D1_46") (pintype "bidirectional"))
    )
    (net (code "72") (name "unconnected-(U1-GPIO_48{slash}P0.21{slash}QSPI_D1-Pad48)") (class "Default")
      (node (ref "U1") (pin "48") (pinfunction "GPIO_48/P0.21/QSPI_D1_48") (pintype "bidirectional"))
    )
    (net (code "73") (name "unconnected-(U1-GPIO_49{slash}P0.22{slash}QSPI_D2-Pad49)") (class "Default")
      (node (ref "U1") (pin "49") (pinfunction "GPIO_49/P0.22/QSPI_D2_49") (pintype "bidirectional"))
    )
    (net (code "74") (name "unconnected-(U1-GPIO_50{slash}P0.20{slash}QSPI_D0-Pad50)") (class "Default")
      (node (ref "U1") (pin "50") (pinfunction "GPIO_50/P0.20/QSPI_D0_50") (pintype "bidirectional"))
    )
    (net (code "75") (name "unconnected-(U1-GPIO_51{slash}P0.17{slash}QSPI_CS-Pad51)") (class "Default")
      (node (ref "U1") (pin "51") (pinfunction "GPIO_51/P0.17/QSPI_CS_51") (pintype "bidirectional"))
    )
    (net (code "76") (name "unconnected-(U1-GPIO_52{slash}P0.19{slash}QSPI_CLK-Pad52)") (class "Default")
      (node (ref "U1") (pin "52") (pinfunction "GPIO_52/P0.19/QSPI_CLK_52") (pintype "bidirectional"))
    )
    (net (code "77") (name "unconnected-(U1-RSVD13-Pad13)") (class "Default")
      (node (ref "U1") (pin "13") (pinfunction "RSVD13_13") (pintype "passive"))
    )
  )
)
